# Sheet1.net
KiCad netlist of a schematic drawn in Altium Designer
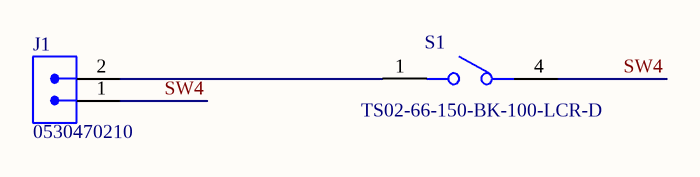
[diagram p0: Sheet1.SchDoc]

(export (version "E")
  (design (tool "Eeschema 10.0.6"))
  (components
    (comp (ref "J1")
      (value "0530470210")
      (footprint "2POS")
      (description "Connector Header Through Hole 2 position 0.049\" (1.25mm)")
      (libsource (lib "Molex") (part "0530470210"))
    )
    (comp (ref "S1")
      (value "TS02-66-150-BK-100-LCR-D")
      (footprint "6mm x 6mm")
      (description "Tactile Switch SPST-NO Top Actuated Through Hole")
      (libsource (lib "Same Sky") (part "TS02-66-150-BK-100-LCR-D"))
    )
  )
  (nets
    (net (code "1") (name "/SW4") (class "Default")
      (node (ref "J1") (pin "1") (pinfunction "1_1") (pintype "passive"))
      (node (ref "S1") (pin "4") (pinfunction "4_4") (pintype "passive"))
    )
    (net (code "2") (name "Net-(J1-Pad2)") (class "Default")
      (node (ref "J1") (pin "2") (pinfunction "2_2") (pintype "passive"))
      (node (ref "S1") (pin "1") (pinfunction "1_1") (pintype "passive"))
    )
  )
)
